# Adafruit_MSA301.net
KiCad netlist of a schematic drawn in EAGLE
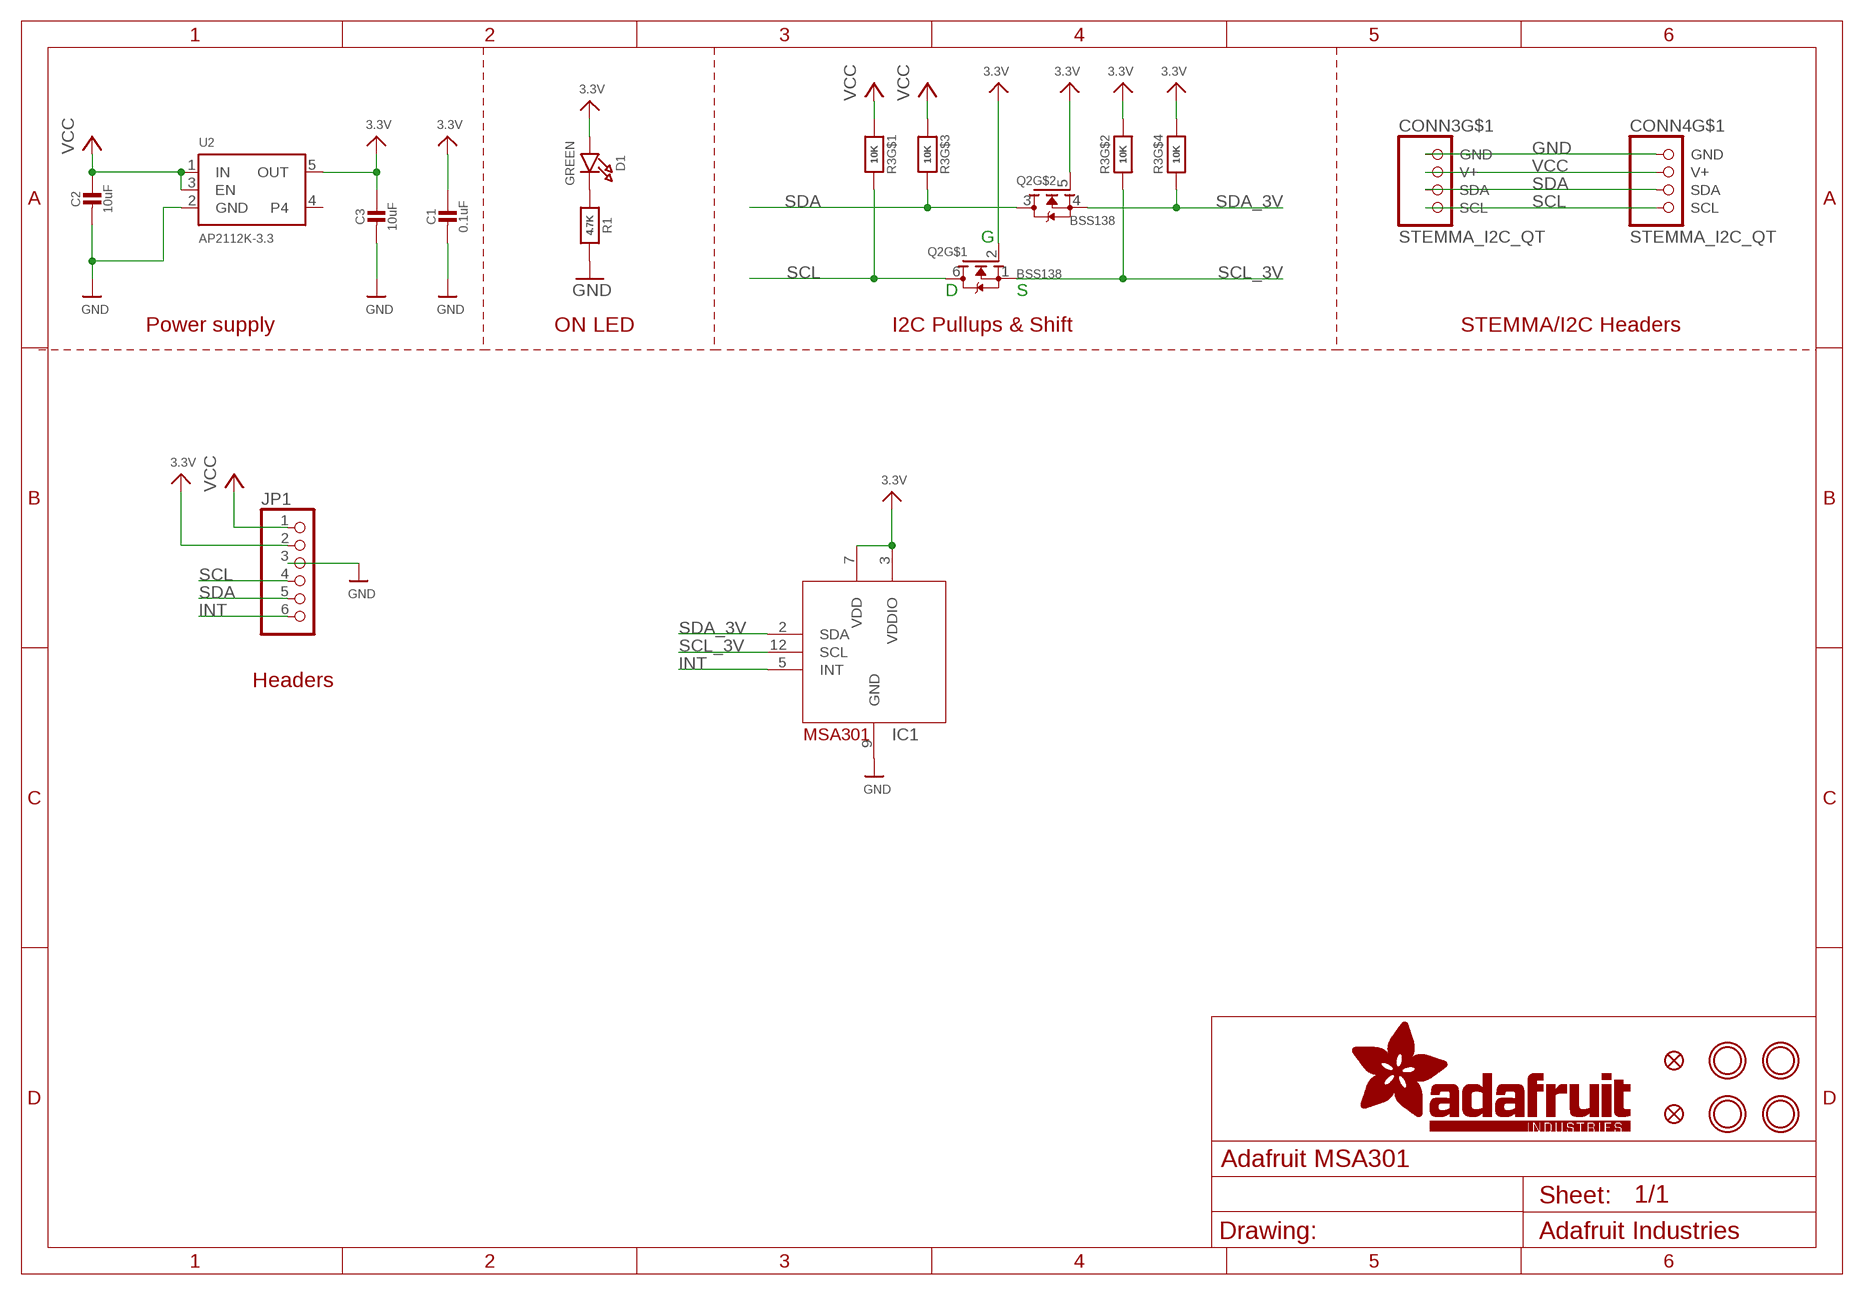
[diagram p0: schematic, sheet 1]

(export (version "E")
  (design (tool "Eeschema 10.0.6"))
  (components
    (comp (ref "C1")
      (value "0.1uF")
      (footprint "eagle-import:0603-NO")
      (libsource (lib "eagle-import") (part "CAP_CERAMIC0603_NO"))
    )
    (comp (ref "C2")
      (value "10uF")
      (footprint "eagle-import:0805-NO")
      (libsource (lib "eagle-import") (part "CAP_CERAMIC0805-NOOUTLINE"))
    )
    (comp (ref "C3")
      (value "10uF")
      (footprint "eagle-import:0805-NO")
      (libsource (lib "eagle-import") (part "CAP_CERAMIC0805-NOOUTLINE"))
    )
    (comp (ref "CONN3")
      (value "STEMMA_I2C_QT")
      (footprint "eagle-import:JST_SH4")
      (libsource (lib "eagle-import") (part "STEMMA_I2C_QT"))
    )
    (comp (ref "CONN4")
      (value "STEMMA_I2C_QT")
      (footprint "eagle-import:JST_SH4")
      (libsource (lib "eagle-import") (part "STEMMA_I2C_QT"))
    )
    (comp (ref "D1")
      (value "GREEN")
      (footprint "eagle-import:CHIPLED_0603_NOOUTLINE")
      (libsource (lib "eagle-import") (part "LED0603_NOOUTLINE"))
    )
    (comp (ref "FID3")
      (value "FIDUCIAL_1MM")
      (footprint "eagle-import:FIDUCIAL_1MM")
      (libsource (lib "eagle-import") (part "FIDUCIAL_1MM"))
    )
    (comp (ref "FID4")
      (value "FIDUCIAL_1MM")
      (footprint "eagle-import:FIDUCIAL_1MM")
      (libsource (lib "eagle-import") (part "FIDUCIAL_1MM"))
    )
    (comp (ref "IC1")
      (value "MSA301")
      (footprint "eagle-import:LGA12_2X2MM")
      (libsource (lib "eagle-import") (part "MSA301"))
    )
    (comp (ref "JP1")
      (value "HEADER-1X670MIL")
      (footprint "eagle-import:1X06_ROUND_70")
      (libsource (lib "eagle-import") (part "HEADER-1X670MIL"))
    )
    (comp (ref "Q2")
      (value "BSS138")
      (footprint "eagle-import:SOT363")
      (libsource (lib "eagle-import") (part "MOSFET-N_DUAL"))
    )
    (comp (ref "R1")
      (value "4.7K")
      (footprint "eagle-import:0603-NO")
      (libsource (lib "eagle-import") (part "RESISTOR_0603_NOOUT"))
    )
    (comp (ref "R3")
      (value "10K")
      (footprint "eagle-import:RESPACK_4X0603")
      (libsource (lib "eagle-import") (part "RESISTOR_4PACK"))
    )
    (comp (ref "U$1")
      (value "MOUNTINGHOLE2.5")
      (footprint "eagle-import:MOUNTINGHOLE_2.5_PLATED")
      (libsource (lib "eagle-import") (part "MOUNTINGHOLE2.5"))
    )
    (comp (ref "U$17")
      (value "MOUNTINGHOLE2.5")
      (footprint "eagle-import:MOUNTINGHOLE_2.5_PLATED")
      (libsource (lib "eagle-import") (part "MOUNTINGHOLE2.5"))
    )
    (comp (ref "U$19")
      (value "MOUNTINGHOLE2.5")
      (footprint "eagle-import:MOUNTINGHOLE_2.5_PLATED")
      (libsource (lib "eagle-import") (part "MOUNTINGHOLE2.5"))
    )
    (comp (ref "U$21")
      (value "MOUNTINGHOLE2.5")
      (footprint "eagle-import:MOUNTINGHOLE_2.5_PLATED")
      (libsource (lib "eagle-import") (part "MOUNTINGHOLE2.5"))
    )
    (comp (ref "U2")
      (value "AP2112K-3.3")
      (footprint "eagle-import:SOT23-5")
      (libsource (lib "eagle-import") (part "VREG_SOT23-5"))
    )
  )
  (nets
    (net (code "1") (name "/INT") (class "Default")
      (node (ref "IC1") (pin "5") (pinfunction "INT_5") (pintype "output"))
      (node (ref "JP1") (pin "6") (pinfunction "6_6") (pintype "passive"))
    )
    (net (code "2") (name "/SCL") (class "Default")
      (node (ref "CONN3") (pin "4") (pinfunction "SCL_4") (pintype "passive"))
      (node (ref "CONN4") (pin "4") (pinfunction "SCL_4") (pintype "passive"))
      (node (ref "JP1") (pin "4") (pinfunction "4_4") (pintype "passive"))
      (node (ref "Q2") (pin "6") (pinfunction "D_6") (pintype "bidirectional"))
      (node (ref "R3") (pin "8") (pinfunction "2_8") (pintype "passive"))
    )
    (net (code "3") (name "/SCL_3V") (class "Default")
      (node (ref "IC1") (pin "12") (pinfunction "SCL_12") (pintype "bidirectional"))
      (node (ref "Q2") (pin "1") (pinfunction "S_1") (pintype "bidirectional"))
      (node (ref "R3") (pin "7") (pinfunction "2_7") (pintype "passive"))
    )
    (net (code "4") (name "/SDA") (class "Default")
      (node (ref "CONN3") (pin "3") (pinfunction "SDA_3") (pintype "passive"))
      (node (ref "CONN4") (pin "3") (pinfunction "SDA_3") (pintype "passive"))
      (node (ref "JP1") (pin "5") (pinfunction "5_5") (pintype "passive"))
      (node (ref "Q2") (pin "3") (pinfunction "D_3") (pintype "bidirectional"))
      (node (ref "R3") (pin "6") (pinfunction "2_6") (pintype "passive"))
    )
    (net (code "5") (name "/SDA_3V") (class "Default")
      (node (ref "IC1") (pin "2") (pinfunction "SDA_2") (pintype "bidirectional"))
      (node (ref "Q2") (pin "4") (pinfunction "S_4") (pintype "bidirectional"))
      (node (ref "R3") (pin "5") (pinfunction "2_5") (pintype "passive"))
    )
    (net (code "6") (name "3.3V") (class "Default")
      (node (ref "C1") (pin "1") (pinfunction "1_1") (pintype "passive"))
      (node (ref "C3") (pin "1") (pinfunction "1_1") (pintype "passive"))
      (node (ref "D1") (pin "A") (pinfunction "A_A") (pintype "passive"))
      (node (ref "IC1") (pin "3") (pinfunction "VDDIO_3") (pintype "power_in"))
      (node (ref "IC1") (pin "7") (pinfunction "VDD_7") (pintype "power_in"))
      (node (ref "JP1") (pin "2") (pinfunction "2_2") (pintype "passive"))
      (node (ref "Q2") (pin "2") (pinfunction "G_2") (pintype "bidirectional"))
      (node (ref "Q2") (pin "5") (pinfunction "G_5") (pintype "bidirectional"))
      (node (ref "R3") (pin "2") (pinfunction "1_2") (pintype "passive"))
      (node (ref "R3") (pin "4") (pinfunction "1_4") (pintype "passive"))
      (node (ref "U2") (pin "5") (pinfunction "OUT_5") (pintype "power_in"))
    )
    (net (code "7") (name "GND") (class "Default")
      (node (ref "C1") (pin "2") (pinfunction "2_2") (pintype "passive"))
      (node (ref "C2") (pin "2") (pinfunction "2_2") (pintype "passive"))
      (node (ref "C3") (pin "2") (pinfunction "2_2") (pintype "passive"))
      (node (ref "CONN3") (pin "1") (pinfunction "GND_1") (pintype "passive"))
      (node (ref "CONN4") (pin "1") (pinfunction "GND_1") (pintype "passive"))
      (node (ref "IC1") (pin "9") (pinfunction "GND_9") (pintype "power_in"))
      (node (ref "JP1") (pin "3") (pinfunction "3_3") (pintype "passive"))
      (node (ref "R1") (pin "2") (pinfunction "2_2") (pintype "passive"))
      (node (ref "U2") (pin "2") (pinfunction "GND_2") (pintype "power_in"))
    )
    (net (code "8") (name "Net-(D1-PadC)") (class "Default")
      (node (ref "D1") (pin "C") (pinfunction "C_C") (pintype "passive"))
      (node (ref "R1") (pin "1") (pinfunction "1_1") (pintype "passive"))
    )
    (net (code "9") (name "VCC") (class "Default")
      (node (ref "C2") (pin "1") (pinfunction "1_1") (pintype "passive"))
      (node (ref "CONN3") (pin "2") (pinfunction "V+_2") (pintype "passive"))
      (node (ref "CONN4") (pin "2") (pinfunction "V+_2") (pintype "passive"))
      (node (ref "JP1") (pin "1") (pinfunction "1_1") (pintype "passive"))
      (node (ref "R3") (pin "1") (pinfunction "1_1") (pintype "passive"))
      (node (ref "R3") (pin "3") (pinfunction "1_3") (pintype "passive"))
      (node (ref "U2") (pin "1") (pinfunction "IN_1") (pintype "power_in"))
      (node (ref "U2") (pin "3") (pinfunction "EN_3") (pintype "input"))
    )
    (net (code "10") (name "unconnected-(U2-P4-Pad4)") (class "Default")
      (node (ref "U2") (pin "4") (pinfunction "P4_4") (pintype "bidirectional"))
    )
  )
)
